# NSSTC.net
KiCad netlist of a schematic drawn in Altium Designer
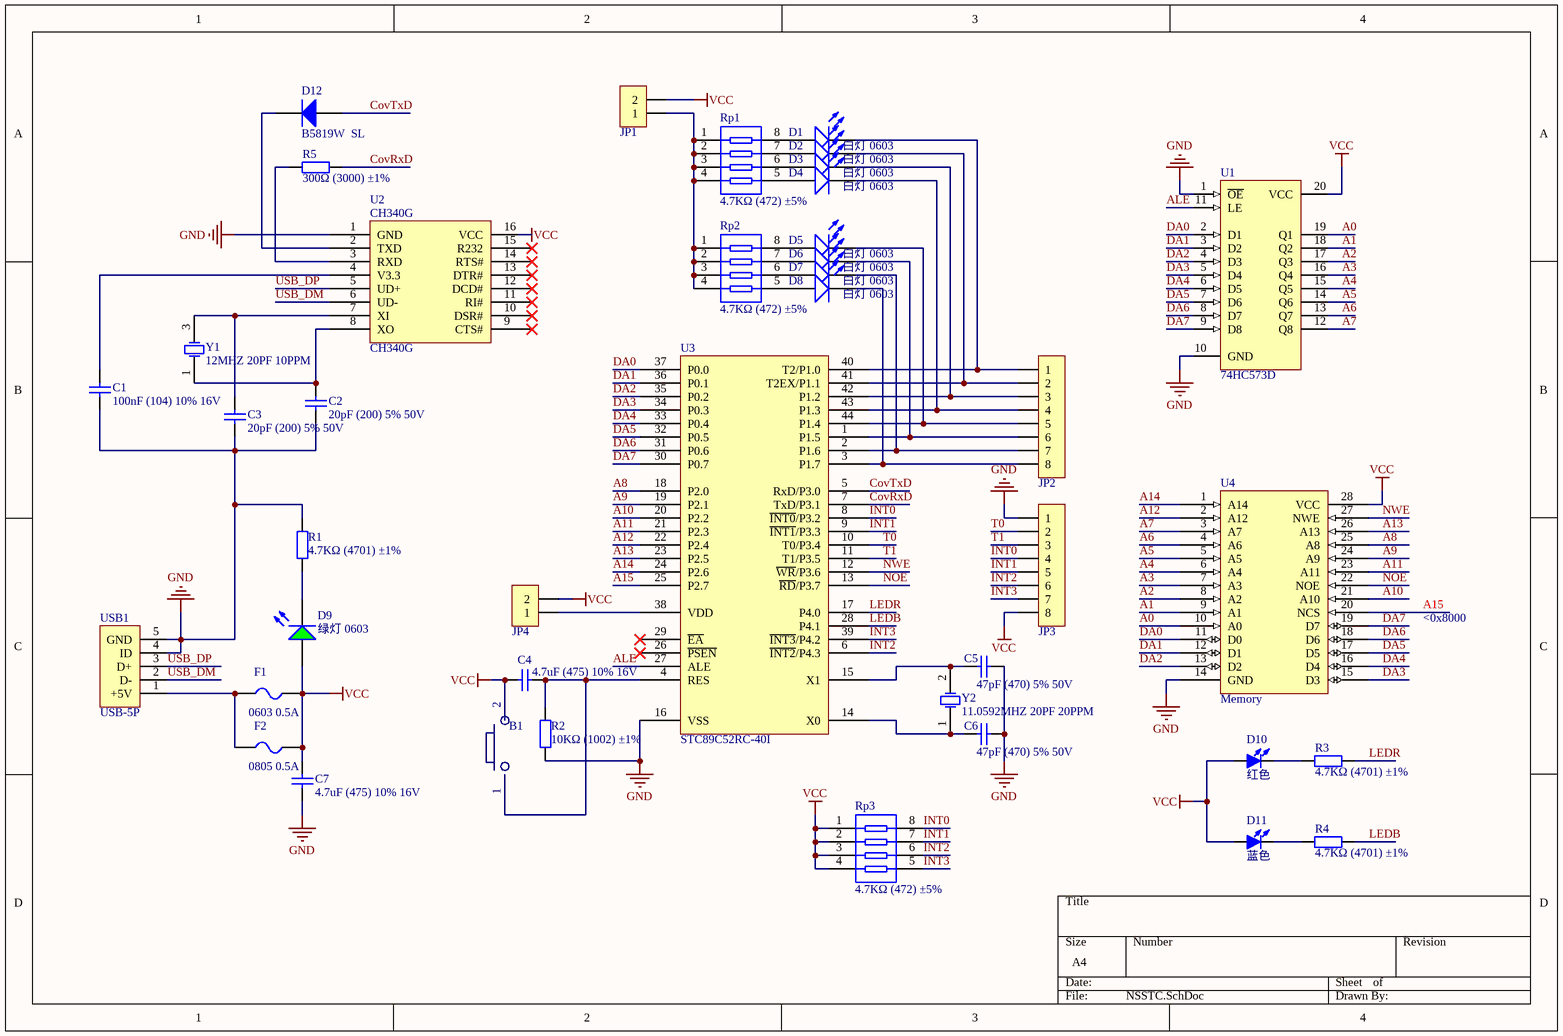
[diagram p0: NSSTC.SchDoc]

(export (version "E")
  (design (tool "Eeschema 10.0.6"))
  (components
    (comp (ref "B1")
      (value "B?")
      (footprint "MetalButton")
      (libsource (lib "MetalButton") (part "MetalButton"))
    )
    (comp (ref "C1")
      (value "100nF (104) 10% 16V")
      (footprint "0402_C")
      (description "贴片电容")
      (libsource (lib "Miscellaneous Devices LC") (part "0402 100nF (104) 10% 16V"))
    )
    (comp (ref "C2")
      (value "20pF (200) 5% 50V")
      (footprint "0402_C")
      (description "贴片电容")
      (libsource (lib "Miscellaneous Devices LC") (part "0402 20pF (200) 5% 50V"))
    )
    (comp (ref "C3")
      (value "20pF (200) 5% 50V")
      (footprint "0402_C")
      (description "贴片电容")
      (libsource (lib "Miscellaneous Devices LC") (part "0402 20pF (200) 5% 50V"))
    )
    (comp (ref "C4")
      (value "4.7uF (475) 10% 16V")
      (footprint "0603_C")
      (description "贴片电容")
      (libsource (lib "Miscellaneous Devices LC") (part "0603 4.7uF (475) 10% 16V"))
    )
    (comp (ref "C5")
      (value "47pF (470) 5% 50V")
      (footprint "0402_C")
      (description "贴片电容")
      (libsource (lib "Miscellaneous Devices LC") (part "0402 47pF (470) 5% 50V"))
    )
    (comp (ref "C6")
      (value "47pF (470) 5% 50V")
      (footprint "0402_C")
      (description "贴片电容")
      (libsource (lib "Miscellaneous Devices LC") (part "0402 47pF (470) 5% 50V"))
    )
    (comp (ref "C7")
      (value "4.7uF (475) 10% 16V")
      (footprint "0603_C")
      (description "贴片电容")
      (libsource (lib "Miscellaneous Devices LC") (part "0603 4.7uF (475) 10% 16V"))
    )
    (comp (ref "D1")
      (value "白灯 0603")
      (footprint "0603_LED_S1")
      (description "发光二极管")
      (libsource (lib "Miscellaneous Devices LC") (part "0603 白灯"))
    )
    (comp (ref "D2")
      (value "白灯 0603")
      (footprint "0603_LED_S1")
      (description "发光二极管")
      (libsource (lib "Miscellaneous Devices LC") (part "0603 白灯"))
    )
    (comp (ref "D3")
      (value "白灯 0603")
      (footprint "0603_LED_S1")
      (description "发光二极管")
      (libsource (lib "Miscellaneous Devices LC") (part "0603 白灯"))
    )
    (comp (ref "D4")
      (value "白灯 0603")
      (footprint "0603_LED_S1")
      (description "发光二极管")
      (libsource (lib "Miscellaneous Devices LC") (part "0603 白灯"))
    )
    (comp (ref "D5")
      (value "白灯 0603")
      (footprint "0603_LED_S1")
      (description "发光二极管")
      (libsource (lib "Miscellaneous Devices LC") (part "0603 白灯"))
    )
    (comp (ref "D6")
      (value "白灯 0603")
      (footprint "0603_LED_S1")
      (description "发光二极管")
      (libsource (lib "Miscellaneous Devices LC") (part "0603 白灯"))
    )
    (comp (ref "D7")
      (value "白灯 0603")
      (footprint "0603_LED_S1")
      (description "发光二极管")
      (libsource (lib "Miscellaneous Devices LC") (part "0603 白灯"))
    )
    (comp (ref "D8")
      (value "白灯 0603")
      (footprint "0603_LED_S1")
      (description "发光二极管")
      (libsource (lib "Miscellaneous Devices LC") (part "0603 白灯"))
    )
    (comp (ref "D9")
      (value "绿灯 0603")
      (footprint "0603_LED_S1")
      (description "发光二极管")
      (libsource (lib "Miscellaneous Devices LC") (part "0603 绿灯"))
    )
    (comp (ref "D10")
      (value "红色")
      (footprint "LED 0805R")
      (description "贴片LED")
      (fields (field (name "版权归属") "源创客"))
      (libsource (lib "9.1   - LED") (part "LED-SMD"))
    )
    (comp (ref "D11")
      (value "蓝色")
      (footprint "LED 0805B")
      (description "贴片LED")
      (fields (field (name "版权归属") "源创客"))
      (libsource (lib "9.1   - LED") (part "LED-SMD"))
    )
    (comp (ref "D12")
      (value "B5819W  SL")
      (footprint "SOD-123")
      (description "肖特基二极管")
      (libsource (lib "Miscellaneous Devices LC") (part "SOD-123 B5819W  SL"))
    )
    (comp (ref "F1")
      (value "0603 0.5A")
      (footprint "FU 0603")
      (description "贴片保险丝")
      (fields (field (name "版权归属") "源创客"))
      (libsource (lib "10.1 - 保险丝-晶振") (part "FU"))
    )
    (comp (ref "F2")
      (value "0805 0.5A")
      (footprint "FU 0805")
      (description "贴片保险丝")
      (fields (field (name "版权归属") "源创客"))
      (libsource (lib "10.1 - 保险丝-晶振") (part "FU"))
    )
    (comp (ref "JP1")
      (value "HDR-1X2")
      (footprint "HDR2.54-LI-2P")
      (description "2P接插件")
      (fields (field (name "版权归属") "源创客"))
      (libsource (lib "4.5   - 接插件-脚距2.54") (part "Header 2"))
    )
    (comp (ref "JP2")
      (value "HDR-1X8")
      (footprint "HDR2.54-LI-8P")
      (description "8P接插件")
      (fields (field (name "版权归属") "源创客"))
      (libsource (lib "4.5   - 接插件-脚距2.54") (part "Header 8"))
    )
    (comp (ref "JP3")
      (value "HDR-1X8")
      (footprint "HDR2.54-LI-8P")
      (description "8P接插件")
      (fields (field (name "版权归属") "源创客"))
      (libsource (lib "4.5   - 接插件-脚距2.54") (part "Header 8"))
    )
    (comp (ref "JP4")
      (value "HDR-1X2")
      (footprint "HDR2.54-LI-2P")
      (description "2P接插件")
      (fields (field (name "版权归属") "源创客"))
      (libsource (lib "4.5   - 接插件-脚距2.54") (part "Header 2"))
    )
    (comp (ref "R1")
      (value "4.7KΩ (4701) ±1%")
      (footprint "0402_R")
      (description "贴片电阻")
      (libsource (lib "Miscellaneous Devices LC") (part "0402 4.7KΩ (4701) 1%"))
    )
    (comp (ref "R2")
      (value "10KΩ (1002) ±1%")
      (footprint "0402_R")
      (description "贴片电阻")
      (libsource (lib "Miscellaneous Devices LC") (part "0402 10KΩ (1002) 1%"))
    )
    (comp (ref "R3")
      (value "4.7KΩ (4701) ±1%")
      (footprint "0402_R")
      (description "贴片电阻")
      (libsource (lib "") (part "0402 4.7KΩ (4701) 1%_1"))
    )
    (comp (ref "R4")
      (value "4.7KΩ (4701) ±1%")
      (footprint "0402_R")
      (description "贴片电阻")
      (libsource (lib "") (part "0402 4.7KΩ (4701) 1%_1"))
    )
    (comp (ref "R5")
      (value "300Ω (3000) ±1%")
      (footprint "0402_R")
      (description "贴片电阻")
      (libsource (lib "Miscellaneous Devices LC") (part "0402 300Ω (3000) 1%"))
    )
    (comp (ref "Rp1")
      (value "4.7KΩ (472) ±5%")
      (footprint "0603_Rx4")
      (description "贴片排阻")
      (libsource (lib "Miscellaneous Devices LC") (part "0603*4  4.7KΩ (472) 5%"))
    )
    (comp (ref "Rp2")
      (value "4.7KΩ (472) ±5%")
      (footprint "0603_Rx4")
      (description "贴片排阻")
      (libsource (lib "Miscellaneous Devices LC") (part "0603*4  4.7KΩ (472) 5%"))
    )
    (comp (ref "Rp3")
      (value "4.7KΩ (472) ±5%")
      (footprint "0603_Rx4")
      (description "贴片排阻")
      (libsource (lib "Miscellaneous Devices LC") (part "0603*4  4.7KΩ (472) 5%"))
    )
    (comp (ref "U1")
      (value "74HC573D")
      (footprint "SOIC-20_300mil")
      (description "74系列逻辑芯片")
      (libsource (lib "Miscellaneous Devices LC") (part "74HC573D_[C5608]"))
    )
    (comp (ref "U2")
      (value "CH340G")
      (footprint "SOIC-16_150mil")
      (description "USB")
      (libsource (lib "Miscellaneous Devices LC") (part "CH340G_[C14267]"))
    )
    (comp (ref "U3")
      (value "STC89C52RC-40I")
      (footprint "LQFP-44_10x10x08P")
      (description "MCU")
      (libsource (lib "Miscellaneous Devices LC") (part "STC89C52RC-40I"))
    )
    (comp (ref "U4") (value "Memory") (footprint "DIP28-600") (libsource (lib "Memory") (part "Memory")))
    (comp (ref "USB1")
      (value "USB-5P")
      (footprint "USB-MICRO_D")
      (description "微型USB母座")
      (fields (field (name "版权归属") "源创客"))
      (libsource (lib "4.1   - 接口类") (part "USB-5P"))
    )
    (comp (ref "Y1")
      (value "12MHZ 20PF 10PPM")
      (footprint "SMD-3225_4P")
      (description "贴片晶振")
      (libsource (lib "Miscellaneous Devices LC") (part "SMD-3225_4P  12MHZ 20PF 10PPM"))
    )
    (comp (ref "Y2")
      (value "11.0592MHZ 20PF 20PPM")
      (footprint "SMD-5032_2P")
      (description "贴片晶振")
      (libsource (lib "Miscellaneous Devices LC") (part "SMD-5032_2P 11.0592MHZ 20PF 20PPM"))
    )
  )
  (nets
    (net (code "1") (name "/A0") (class "Default")
      (node (ref "U1") (pin "19") (pinfunction "Q1_19") (pintype "tri_state"))
      (node (ref "U4") (pin "10") (pinfunction "A0_10") (pintype "input"))
    )
    (net (code "2") (name "/A1") (class "Default")
      (node (ref "U1") (pin "18") (pinfunction "Q2_18") (pintype "tri_state"))
      (node (ref "U4") (pin "9") (pinfunction "A1_9") (pintype "input"))
    )
    (net (code "3") (name "/A2") (class "Default")
      (node (ref "U1") (pin "17") (pinfunction "Q3_17") (pintype "tri_state"))
      (node (ref "U4") (pin "8") (pinfunction "A2_8") (pintype "input"))
    )
    (net (code "4") (name "/A3") (class "Default")
      (node (ref "U1") (pin "16") (pinfunction "Q4_16") (pintype "tri_state"))
      (node (ref "U4") (pin "7") (pinfunction "A3_7") (pintype "input"))
    )
    (net (code "5") (name "/A4") (class "Default")
      (node (ref "U1") (pin "15") (pinfunction "Q5_15") (pintype "tri_state"))
      (node (ref "U4") (pin "6") (pinfunction "A4_6") (pintype "input"))
    )
    (net (code "6") (name "/A5") (class "Default")
      (node (ref "U1") (pin "14") (pinfunction "Q6_14") (pintype "tri_state"))
      (node (ref "U4") (pin "5") (pinfunction "A5_5") (pintype "input"))
    )
    (net (code "7") (name "/A6") (class "Default")
      (node (ref "U1") (pin "13") (pinfunction "Q7_13") (pintype "tri_state"))
      (node (ref "U4") (pin "4") (pinfunction "A6_4") (pintype "input"))
    )
    (net (code "8") (name "/A7") (class "Default")
      (node (ref "U1") (pin "12") (pinfunction "Q8_12") (pintype "tri_state"))
      (node (ref "U4") (pin "3") (pinfunction "A7_3") (pintype "input"))
    )
    (net (code "9") (name "/A8") (class "Default")
      (node (ref "U3") (pin "18") (pinfunction "P2.0_18") (pintype "passive"))
      (node (ref "U4") (pin "25") (pinfunction "A8_25") (pintype "input"))
    )
    (net (code "10") (name "/A9") (class "Default")
      (node (ref "U3") (pin "19") (pinfunction "P2.1_19") (pintype "passive"))
      (node (ref "U4") (pin "24") (pinfunction "A9_24") (pintype "input"))
    )
    (net (code "11") (name "/A10") (class "Default")
      (node (ref "U3") (pin "20") (pinfunction "P2.2_20") (pintype "passive"))
      (node (ref "U4") (pin "21") (pinfunction "A10_21") (pintype "input"))
    )
    (net (code "12") (name "/A11") (class "Default")
      (node (ref "U3") (pin "21") (pinfunction "P2.3_21") (pintype "passive"))
      (node (ref "U4") (pin "23") (pinfunction "A11_23") (pintype "input"))
    )
    (net (code "13") (name "/A12") (class "Default")
      (node (ref "U3") (pin "22") (pinfunction "P2.4_22") (pintype "passive"))
      (node (ref "U4") (pin "2") (pinfunction "A12_2") (pintype "input"))
    )
    (net (code "14") (name "/A13") (class "Default")
      (node (ref "U3") (pin "23") (pinfunction "P2.5_23") (pintype "passive"))
      (node (ref "U4") (pin "26") (pinfunction "A13_26") (pintype "input"))
    )
    (net (code "15") (name "/A14") (class "Default")
      (node (ref "U3") (pin "24") (pinfunction "P2.6_24") (pintype "passive"))
      (node (ref "U4") (pin "1") (pinfunction "A14_1") (pintype "input"))
    )
    (net (code "16") (name "/A15") (class "Default")
      (node (ref "U3") (pin "25") (pinfunction "P2.7_25") (pintype "passive"))
      (node (ref "U4") (pin "20") (pinfunction "NCS_20") (pintype "input"))
    )
    (net (code "17") (name "/ALE") (class "Default")
      (node (ref "U1") (pin "11") (pinfunction "LE_11") (pintype "input"))
      (node (ref "U3") (pin "27") (pinfunction "ALE_27") (pintype "passive"))
    )
    (net (code "18") (name "/CovRxD") (class "Default")
      (node (ref "R5") (pin "2") (pinfunction "2_2") (pintype "passive"))
      (node (ref "U3") (pin "7") (pinfunction "TxD/P3.1_7") (pintype "passive"))
    )
    (net (code "19") (name "/CovTxD") (class "Default")
      (node (ref "D12") (pin "1") (pinfunction "A_1") (pintype "passive"))
      (node (ref "U3") (pin "5") (pinfunction "RxD/P3.0_5") (pintype "passive"))
    )
    (net (code "20") (name "/DA0") (class "Default")
      (node (ref "U1") (pin "2") (pinfunction "D1_2") (pintype "input"))
      (node (ref "U3") (pin "37") (pinfunction "P0.0_37") (pintype "passive"))
      (node (ref "U4") (pin "11") (pinfunction "D0_11") (pintype "bidirectional"))
    )
    (net (code "21") (name "/DA1") (class "Default")
      (node (ref "U1") (pin "3") (pinfunction "D2_3") (pintype "input"))
      (node (ref "U3") (pin "36") (pinfunction "P0.1_36") (pintype "passive"))
      (node (ref "U4") (pin "12") (pinfunction "D1_12") (pintype "bidirectional"))
    )
    (net (code "22") (name "/DA2") (class "Default")
      (node (ref "U1") (pin "4") (pinfunction "D3_4") (pintype "input"))
      (node (ref "U3") (pin "35") (pinfunction "P0.2_35") (pintype "passive"))
      (node (ref "U4") (pin "13") (pinfunction "D2_13") (pintype "bidirectional"))
    )
    (net (code "23") (name "/DA3") (class "Default")
      (node (ref "U1") (pin "5") (pinfunction "D4_5") (pintype "input"))
      (node (ref "U3") (pin "34") (pinfunction "P0.3_34") (pintype "passive"))
      (node (ref "U4") (pin "15") (pinfunction "D3_15") (pintype "bidirectional"))
    )
    (net (code "24") (name "/DA4") (class "Default")
      (node (ref "U1") (pin "6") (pinfunction "D5_6") (pintype "input"))
      (node (ref "U3") (pin "33") (pinfunction "P0.4_33") (pintype "passive"))
      (node (ref "U4") (pin "16") (pinfunction "D4_16") (pintype "bidirectional"))
    )
    (net (code "25") (name "/DA5") (class "Default")
      (node (ref "U1") (pin "7") (pinfunction "D6_7") (pintype "input"))
      (node (ref "U3") (pin "32") (pinfunction "P0.5_32") (pintype "passive"))
      (node (ref "U4") (pin "17") (pinfunction "D5_17") (pintype "bidirectional"))
    )
    (net (code "26") (name "/DA6") (class "Default")
      (node (ref "U1") (pin "8") (pinfunction "D7_8") (pintype "input"))
      (node (ref "U3") (pin "31") (pinfunction "P0.6_31") (pintype "passive"))
      (node (ref "U4") (pin "18") (pinfunction "D6_18") (pintype "bidirectional"))
    )
    (net (code "27") (name "/DA7") (class "Default")
      (node (ref "U1") (pin "9") (pinfunction "D8_9") (pintype "input"))
      (node (ref "U3") (pin "30") (pinfunction "P0.7_30") (pintype "passive"))
      (node (ref "U4") (pin "19") (pinfunction "D7_19") (pintype "bidirectional"))
    )
    (net (code "28") (name "/INT0") (class "Default")
      (node (ref "JP3") (pin "4") (pinfunction "4_4") (pintype "passive"))
      (node (ref "Rp3") (pin "8") (pinfunction "8_8") (pintype "passive"))
      (node (ref "U3") (pin "8") (pinfunction "~{INT0}/P3.2_8") (pintype "passive"))
    )
    (net (code "29") (name "/INT1") (class "Default")
      (node (ref "JP3") (pin "5") (pinfunction "5_5") (pintype "passive"))
      (node (ref "Rp3") (pin "7") (pinfunction "7_7") (pintype "passive"))
      (node (ref "U3") (pin "9") (pinfunction "~{INT1}/P3.3_9") (pintype "passive"))
    )
    (net (code "30") (name "/INT2") (class "Default")
      (node (ref "JP3") (pin "6") (pinfunction "6_6") (pintype "passive"))
      (node (ref "Rp3") (pin "6") (pinfunction "6_6") (pintype "passive"))
      (node (ref "U3") (pin "6") (pinfunction "~{INT2}/P4.3_6") (pintype "passive"))
    )
    (net (code "31") (name "/INT3") (class "Default")
      (node (ref "JP3") (pin "7") (pinfunction "7_7") (pintype "passive"))
      (node (ref "Rp3") (pin "5") (pinfunction "5_5") (pintype "passive"))
      (node (ref "U3") (pin "39") (pinfunction "~{INT3}/P4.2_39") (pintype "passive"))
    )
    (net (code "32") (name "/LEDB") (class "Default")
      (node (ref "R4") (pin "1") (pinfunction "1_1") (pintype "passive"))
      (node (ref "U3") (pin "28") (pinfunction "P4.1_28") (pintype "passive"))
    )
    (net (code "33") (name "/LEDR") (class "Default")
      (node (ref "R3") (pin "1") (pinfunction "1_1") (pintype "passive"))
      (node (ref "U3") (pin "17") (pinfunction "P4.0_17") (pintype "passive"))
    )
    (net (code "34") (name "/NOE") (class "Default")
      (node (ref "U3") (pin "13") (pinfunction "~{RD}/P3.7_13") (pintype "passive"))
      (node (ref "U4") (pin "22") (pinfunction "NOE_22") (pintype "input"))
    )
    (net (code "35") (name "/NWE") (class "Default")
      (node (ref "U3") (pin "12") (pinfunction "~{WR}/P3.6_12") (pintype "passive"))
      (node (ref "U4") (pin "27") (pinfunction "NWE_27") (pintype "input"))
    )
    (net (code "36") (name "/T0") (class "Default")
      (node (ref "JP3") (pin "2") (pinfunction "2_2") (pintype "passive"))
      (node (ref "U3") (pin "10") (pinfunction "T0/P3.4_10") (pintype "passive"))
    )
    (net (code "37") (name "/T1") (class "Default")
      (node (ref "JP3") (pin "3") (pinfunction "3_3") (pintype "passive"))
      (node (ref "U3") (pin "11") (pinfunction "T1/P3.5_11") (pintype "passive"))
    )
    (net (code "38") (name "/USB_DM") (class "Default")
      (node (ref "U2") (pin "6") (pinfunction "UD-_6") (pintype "passive"))
      (node (ref "USB1") (pin "2") (pinfunction "D-_2") (pintype "passive"))
    )
    (net (code "39") (name "/USB_DP") (class "Default")
      (node (ref "U2") (pin "5") (pinfunction "UD+_5") (pintype "passive"))
      (node (ref "USB1") (pin "3") (pinfunction "D+_3") (pintype "passive"))
    )
    (net (code "40") (name "GND") (class "Default")
      (node (ref "C1") (pin "1") (pinfunction "1_1") (pintype "passive"))
      (node (ref "C2") (pin "1") (pinfunction "1_1") (pintype "passive"))
      (node (ref "C3") (pin "1") (pinfunction "1_1") (pintype "passive"))
      (node (ref "C5") (pin "2") (pinfunction "2_2") (pintype "passive"))
      (node (ref "C6") (pin "2") (pinfunction "2_2") (pintype "passive"))
      (node (ref "C7") (pin "1") (pinfunction "1_1") (pintype "passive"))
      (node (ref "JP3") (pin "1") (pinfunction "1_1") (pintype "passive"))
      (node (ref "R1") (pin "2") (pinfunction "2_2") (pintype "passive"))
      (node (ref "R2") (pin "1") (pinfunction "1_1") (pintype "passive"))
      (node (ref "U1") (pin "1") (pinfunction "~{OE}_1") (pintype "input"))
      (node (ref "U1") (pin "10") (pinfunction "GND_10") (pintype "power_in"))
      (node (ref "U2") (pin "1") (pinfunction "GND_1") (pintype "passive"))
      (node (ref "U3") (pin "16") (pinfunction "VSS_16") (pintype "passive"))
      (node (ref "U4") (pin "14") (pinfunction "GND_14") (pintype "power_in"))
      (node (ref "USB1") (pin "4") (pinfunction "ID_4") (pintype "passive"))
      (node (ref "USB1") (pin "5") (pinfunction "GND_5") (pintype "passive"))
    )
    (net (code "41") (name "Net-(D1-PadA)") (class "Default")
      (node (ref "D1") (pin "A") (pinfunction "A_A") (pintype "passive"))
      (node (ref "Rp1") (pin "8") (pinfunction "8_8") (pintype "passive"))
    )
    (net (code "42") (name "Net-(D2-PadA)") (class "Default")
      (node (ref "D2") (pin "A") (pinfunction "A_A") (pintype "passive"))
      (node (ref "Rp1") (pin "7") (pinfunction "7_7") (pintype "passive"))
    )
    (net (code "43") (name "Net-(D3-PadA)") (class "Default")
      (node (ref "D3") (pin "A") (pinfunction "A_A") (pintype "passive"))
      (node (ref "Rp1") (pin "6") (pinfunction "6_6") (pintype "passive"))
    )
    (net (code "44") (name "Net-(D4-PadA)") (class "Default")
      (node (ref "D4") (pin "A") (pinfunction "A_A") (pintype "passive"))
      (node (ref "Rp1") (pin "5") (pinfunction "5_5") (pintype "passive"))
    )
    (net (code "45") (name "Net-(D5-PadA)") (class "Default")
      (node (ref "D5") (pin "A") (pinfunction "A_A") (pintype "passive"))
      (node (ref "Rp2") (pin "8") (pinfunction "8_8") (pintype "passive"))
    )
    (net (code "46") (name "Net-(D6-PadA)") (class "Default")
      (node (ref "D6") (pin "A") (pinfunction "A_A") (pintype "passive"))
      (node (ref "Rp2") (pin "7") (pinfunction "7_7") (pintype "passive"))
    )
    (net (code "47") (name "Net-(D7-PadA)") (class "Default")
      (node (ref "D7") (pin "A") (pinfunction "A_A") (pintype "passive"))
      (node (ref "Rp2") (pin "6") (pinfunction "6_6") (pintype "passive"))
    )
    (net (code "48") (name "Net-(D8-PadA)") (class "Default")
      (node (ref "D8") (pin "A") (pinfunction "A_A") (pintype "passive"))
      (node (ref "Rp2") (pin "5") (pinfunction "5_5") (pintype "passive"))
    )
    (net (code "49") (name "Net-(D9-PadK)") (class "Default")
      (node (ref "D9") (pin "K") (pinfunction "K_K") (pintype "passive"))
      (node (ref "R1") (pin "1") (pinfunction "1_1") (pintype "passive"))
    )
    (net (code "50") (name "Net-(D10-K)") (class "Default")
      (node (ref "D10") (pin "2") (pinfunction "K_2") (pintype "passive"))
      (node (ref "R3") (pin "2") (pinfunction "2_2") (pintype "passive"))
    )
    (net (code "51") (name "Net-(D11-K)") (class "Default")
      (node (ref "D11") (pin "2") (pinfunction "K_2") (pintype "passive"))
      (node (ref "R4") (pin "2") (pinfunction "2_2") (pintype "passive"))
    )
    (net (code "52") (name "Net-(D12-K)") (class "Default")
      (node (ref "D12") (pin "2") (pinfunction "K_2") (pintype "passive"))
      (node (ref "U2") (pin "2") (pinfunction "TXD_2") (pintype "passive"))
    )
    (net (code "53") (name "Net-(JP1-Pad1)") (class "Default")
      (node (ref "JP1") (pin "1") (pinfunction "1_1") (pintype "passive"))
      (node (ref "Rp1") (pin "1") (pinfunction "1_1") (pintype "passive"))
      (node (ref "Rp1") (pin "2") (pinfunction "2_2") (pintype "passive"))
      (node (ref "Rp1") (pin "3") (pinfunction "3_3") (pintype "passive"))
      (node (ref "Rp1") (pin "4") (pinfunction "4_4") (pintype "passive"))
      (node (ref "Rp2") (pin "1") (pinfunction "1_1") (pintype "passive"))
      (node (ref "Rp2") (pin "2") (pinfunction "2_2") (pintype "passive"))
      (node (ref "Rp2") (pin "3") (pinfunction "3_3") (pintype "passive"))
      (node (ref "Rp2") (pin "4") (pinfunction "4_4") (pintype "passive"))
    )
    (net (code "54") (name "Net-(U2-RXD)") (class "Default")
      (node (ref "R5") (pin "1") (pinfunction "1_1") (pintype "passive"))
      (node (ref "U2") (pin "3") (pinfunction "RXD_3") (pintype "passive"))
    )
    (net (code "55") (name "Net-(U2-V3.3)") (class "Default")
      (node (ref "C1") (pin "2") (pinfunction "2_2") (pintype "passive"))
      (node (ref "U2") (pin "4") (pinfunction "V3.3_4") (pintype "passive"))
    )
    (net (code "56") (name "Net-(U2-XI)") (class "Default")
      (node (ref "C3") (pin "2") (pinfunction "2_2") (pintype "passive"))
      (node (ref "U2") (pin "7") (pinfunction "XI_7") (pintype "passive"))
      (node (ref "Y1") (pin "3") (pinfunction "OSC2_3") (pintype "passive"))
    )
    (net (code "57") (name "Net-(U2-XO)") (class "Default")
      (node (ref "C2") (pin "2") (pinfunction "2_2") (pintype "passive"))
      (node (ref "U2") (pin "8") (pinfunction "XO_8") (pintype "passive"))
      (node (ref "Y1") (pin "1") (pinfunction "OSC1_1") (pintype "passive"))
    )
    (net (code "58") (name "Net-(U3-P1.2)") (class "Default")
      (node (ref "D3") (pin "K") (pinfunction "K_K") (pintype "passive"))
      (node (ref "JP2") (pin "3") (pinfunction "3_3") (pintype "passive"))
      (node (ref "U3") (pin "42") (pinfunction "P1.2_42") (pintype "passive"))
    )
    (net (code "59") (name "Net-(U3-P1.3)") (class "Default")
      (node (ref "D4") (pin "K") (pinfunction "K_K") (pintype "passive"))
      (node (ref "JP2") (pin "4") (pinfunction "4_4") (pintype "passive"))
      (node (ref "U3") (pin "43") (pinfunction "P1.3_43") (pintype "passive"))
    )
    (net (code "60") (name "Net-(U3-P1.4)") (class "Default")
      (node (ref "D5") (pin "K") (pinfunction "K_K") (pintype "passive"))
      (node (ref "JP2") (pin "5") (pinfunction "5_5") (pintype "passive"))
      (node (ref "U3") (pin "44") (pinfunction "P1.4_44") (pintype "passive"))
    )
    (net (code "61") (name "Net-(U3-P1.5)") (class "Default")
      (node (ref "D6") (pin "K") (pinfunction "K_K") (pintype "passive"))
      (node (ref "JP2") (pin "6") (pinfunction "6_6") (pintype "passive"))
      (node (ref "U3") (pin "1") (pinfunction "P1.5_1") (pintype "passive"))
    )
    (net (code "62") (name "Net-(U3-P1.6)") (class "Default")
      (node (ref "D7") (pin "K") (pinfunction "K_K") (pintype "passive"))
      (node (ref "JP2") (pin "7") (pinfunction "7_7") (pintype "passive"))
      (node (ref "U3") (pin "2") (pinfunction "P1.6_2") (pintype "passive"))
    )
    (net (code "63") (name "Net-(U3-P1.7)") (class "Default")
      (node (ref "D8") (pin "K") (pinfunction "K_K") (pintype "passive"))
      (node (ref "JP2") (pin "8") (pinfunction "8_8") (pintype "passive"))
      (node (ref "U3") (pin "3") (pinfunction "P1.7_3") (pintype "passive"))
    )
    (net (code "64") (name "Net-(U3-RES)") (class "Default")
      (node (ref "B1") (pin "1") (pinfunction "1_1") (pintype "passive"))
      (node (ref "C4") (pin "1") (pinfunction "1_1") (pintype "passive"))
      (node (ref "R2") (pin "2") (pinfunction "2_2") (pintype "passive"))
      (node (ref "U3") (pin "4") (pinfunction "RES_4") (pintype "passive"))
    )
    (net (code "65") (name "Net-(U3-T2EX{slash}P1.1)") (class "Default")
      (node (ref "D2") (pin "K") (pinfunction "K_K") (pintype "passive"))
      (node (ref "JP2") (pin "2") (pinfunction "2_2") (pintype "passive"))
      (node (ref "U3") (pin "41") (pinfunction "T2EX/P1.1_41") (pintype "passive"))
    )
    (net (code "66") (name "Net-(U3-T2{slash}P1.0)") (class "Default")
      (node (ref "D1") (pin "K") (pinfunction "K_K") (pintype "passive"))
      (node (ref "JP2") (pin "1") (pinfunction "1_1") (pintype "passive"))
      (node (ref "U3") (pin "40") (pinfunction "T2/P1.0_40") (pintype "passive"))
    )
    (net (code "67") (name "Net-(U3-VDD)") (class "Default")
      (node (ref "JP4") (pin "1") (pinfunction "1_1") (pintype "passive"))
      (node (ref "U3") (pin "38") (pinfunction "VDD_38") (pintype "passive"))
    )
    (net (code "68") (name "Net-(U3-X0)") (class "Default")
      (node (ref "C6") (pin "1") (pinfunction "1_1") (pintype "passive"))
      (node (ref "U3") (pin "14") (pinfunction "X0_14") (pintype "passive"))
      (node (ref "Y2") (pin "1") (pinfunction "OSC1_1") (pintype "passive"))
    )
    (net (code "69") (name "Net-(U3-X1)") (class "Default")
      (node (ref "C5") (pin "1") (pinfunction "1_1") (pintype "passive"))
      (node (ref "U3") (pin "15") (pinfunction "X1_15") (pintype "passive"))
      (node (ref "Y2") (pin "2") (pinfunction "OSC2_2") (pintype "passive"))
    )
    (net (code "70") (name "Net-(USB1-+5V)") (class "Default")
      (node (ref "F1") (pin "2") (pinfunction "2_2") (pintype "passive"))
      (node (ref "F2") (pin "1") (pinfunction "1_1") (pintype "passive"))
      (node (ref "USB1") (pin "1") (pinfunction "+5V_1") (pintype "passive"))
    )
    (net (code "71") (name "VCC") (class "Default")
      (node (ref "B1") (pin "2") (pinfunction "2_2") (pintype "passive"))
      (node (ref "C4") (pin "2") (pinfunction "2_2") (pintype "passive"))
      (node (ref "C7") (pin "2") (pinfunction "2_2") (pintype "passive"))
      (node (ref "D10") (pin "1") (pinfunction "A_1") (pintype "passive"))
      (node (ref "D11") (pin "1") (pinfunction "A_1") (pintype "passive"))
      (node (ref "D9") (pin "A") (pinfunction "A_A") (pintype "passive"))
      (node (ref "F1") (pin "1") (pinfunction "1_1") (pintype "passive"))
      (node (ref "F2") (pin "2") (pinfunction "2_2") (pintype "passive"))
      (node (ref "JP1") (pin "2") (pinfunction "2_2") (pintype "passive"))
      (node (ref "JP3") (pin "8") (pinfunction "8_8") (pintype "passive"))
      (node (ref "JP4") (pin "2") (pinfunction "2_2") (pintype "passive"))
      (node (ref "Rp3") (pin "1") (pinfunction "1_1") (pintype "passive"))
      (node (ref "Rp3") (pin "2") (pinfunction "2_2") (pintype "passive"))
      (node (ref "Rp3") (pin "3") (pinfunction "3_3") (pintype "passive"))
      (node (ref "Rp3") (pin "4") (pinfunction "4_4") (pintype "passive"))
      (node (ref "U1") (pin "20") (pinfunction "VCC_20") (pintype "power_in"))
      (node (ref "U2") (pin "16") (pinfunction "VCC_16") (pintype "passive"))
      (node (ref "U4") (pin "28") (pinfunction "VCC_28") (pintype "power_in"))
    )
    (net (code "72") (name "unconnected-(U2-CTS#-Pad9)") (class "Default")
      (node (ref "U2") (pin "9") (pinfunction "CTS#_9") (pintype "passive+no_connect"))
    )
    (net (code "73") (name "unconnected-(U2-DCD#-Pad12)") (class "Default")
      (node (ref "U2") (pin "12") (pinfunction "DCD#_12") (pintype "passive+no_connect"))
    )
    (net (code "74") (name "unconnected-(U2-DSR#-Pad10)") (class "Default")
      (node (ref "U2") (pin "10") (pinfunction "DSR#_10") (pintype "passive+no_connect"))
    )
    (net (code "75") (name "unconnected-(U2-DTR#-Pad13)") (class "Default")
      (node (ref "U2") (pin "13") (pinfunction "DTR#_13") (pintype "passive+no_connect"))
    )
    (net (code "76") (name "unconnected-(U2-R232-Pad15)") (class "Default")
      (node (ref "U2") (pin "15") (pinfunction "R232_15") (pintype "passive+no_connect"))
    )
    (net (code "77") (name "unconnected-(U2-RI#-Pad11)") (class "Default")
      (node (ref "U2") (pin "11") (pinfunction "RI#_11") (pintype "passive+no_connect"))
    )
    (net (code "78") (name "unconnected-(U2-RTS#-Pad14)") (class "Default")
      (node (ref "U2") (pin "14") (pinfunction "RTS#_14") (pintype "passive+no_connect"))
    )
    (net (code "79") (name "unconnected-(U3-~{EA}-Pad29)") (class "Default")
      (node (ref "U3") (pin "29") (pinfunction "~{EA}_29") (pintype "passive+no_connect"))
    )
    (net (code "80") (name "unconnected-(U3-~{PSEN}-Pad26)") (class "Default")
      (node (ref "U3") (pin "26") (pinfunction "~{PSEN}_26") (pintype "passive+no_connect"))
    )
  )
)
